# 05_IO_CONN.net
KiCad netlist of a schematic drawn in Altium Designer
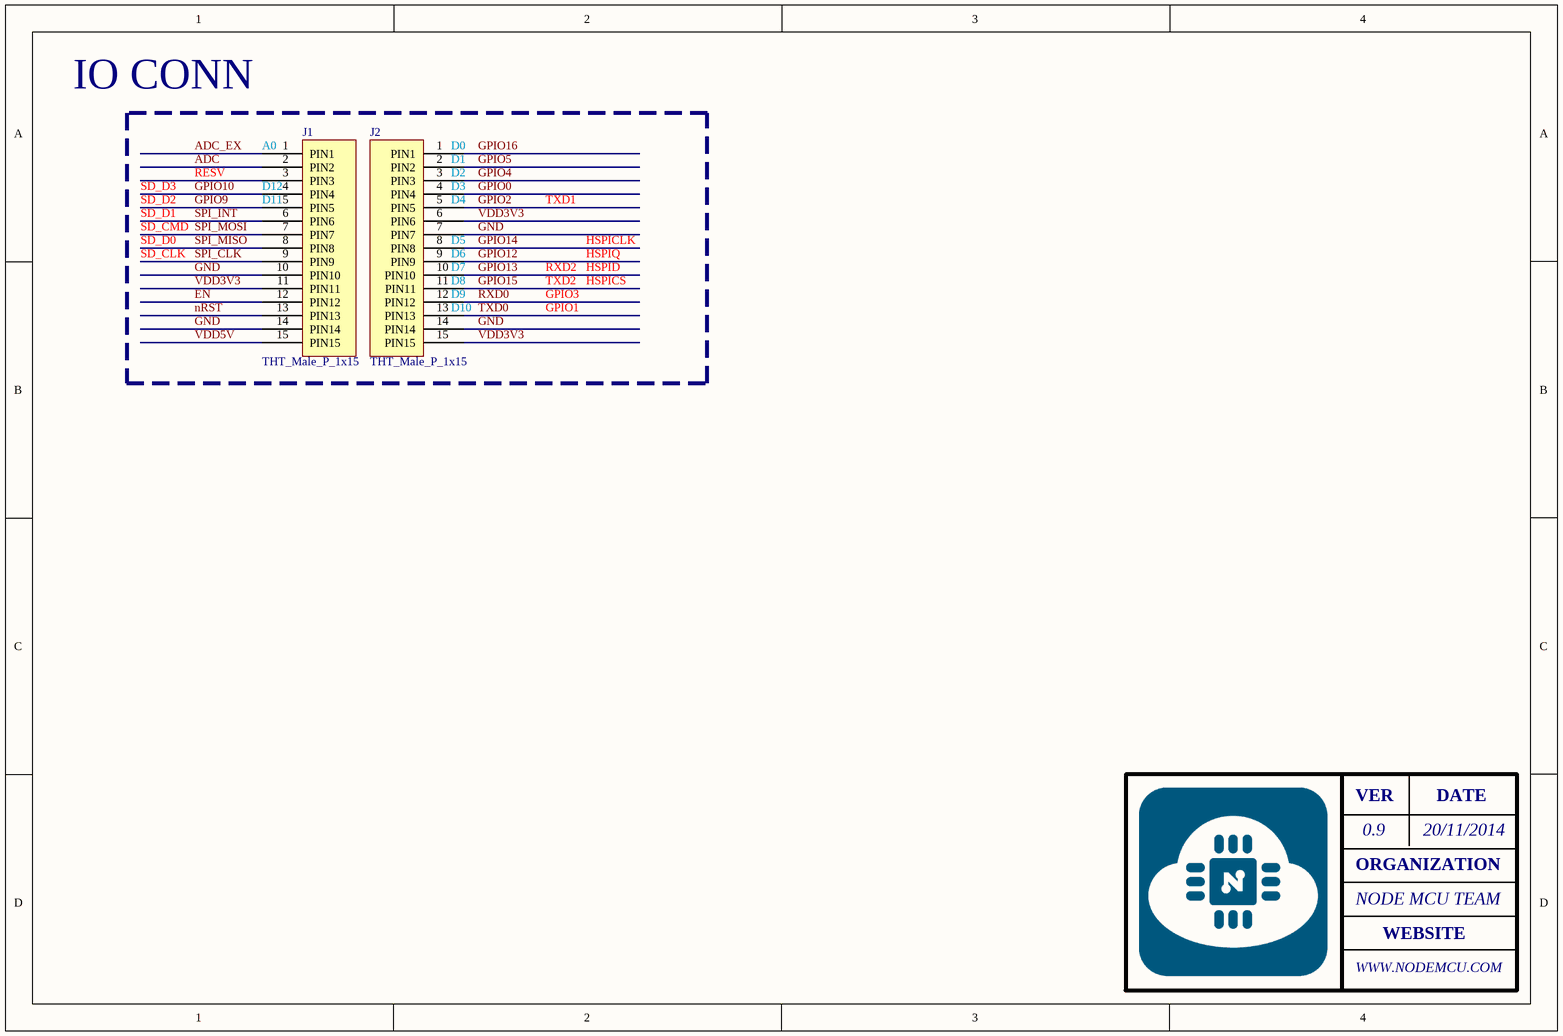
[diagram p0: 05_IO_CONN.SchDoc]

(export (version "E")
  (design (tool "Eeschema 10.0.6"))
  (components
    (comp (ref "J1")
      (value "THT_Male_P_1x15")
      (footprint "THT_Male_P_1x15-2.54mm")
      (description "THT Male pin header strip 1x15")
      (libsource (lib "") (part "THT_Male_P_1x15_1"))
    )
    (comp (ref "J2")
      (value "THT_Male_P_1x15")
      (footprint "THT_Male_P_1x15-2.54mm")
      (description "THT Male pin header strip 1x15")
      (libsource (lib "Vowstar_Connector") (part "THT_Male_P_1x15"))
    )
  )
  (nets
    (net (code "1") (name "/ADC") (class "Default")
      (node (ref "J1") (pin "2") (pinfunction "PIN2_2") (pintype "passive"))
    )
    (net (code "2") (name "/ADC_EX") (class "Default")
      (node (ref "J1") (pin "1") (pinfunction "PIN1_1") (pintype "passive"))
    )
    (net (code "3") (name "/EN") (class "Default")
      (node (ref "J1") (pin "12") (pinfunction "PIN12_12") (pintype "passive"))
    )
    (net (code "4") (name "/GND") (class "Default")
      (node (ref "J1") (pin "10") (pinfunction "PIN10_10") (pintype "passive"))
      (node (ref "J1") (pin "14") (pinfunction "PIN14_14") (pintype "passive"))
      (node (ref "J2") (pin "14") (pinfunction "PIN14_14") (pintype "passive"))
      (node (ref "J2") (pin "7") (pinfunction "PIN7_7") (pintype "passive"))
    )
    (net (code "5") (name "/GPIO0") (class "Default")
      (node (ref "J2") (pin "4") (pinfunction "PIN4_4") (pintype "passive"))
    )
    (net (code "6") (name "/GPIO2") (class "Default")
      (node (ref "J2") (pin "5") (pinfunction "PIN5_5") (pintype "passive"))
    )
    (net (code "7") (name "/GPIO4") (class "Default")
      (node (ref "J2") (pin "3") (pinfunction "PIN3_3") (pintype "passive"))
    )
    (net (code "8") (name "/GPIO5") (class "Default")
      (node (ref "J2") (pin "2") (pinfunction "PIN2_2") (pintype "passive"))
    )
    (net (code "9") (name "/GPIO9") (class "Default")
      (node (ref "J1") (pin "5") (pinfunction "PIN5_5") (pintype "passive"))
    )
    (net (code "10") (name "/GPIO10") (class "Default")
      (node (ref "J1") (pin "4") (pinfunction "PIN4_4") (pintype "passive"))
    )
    (net (code "11") (name "/GPIO12") (class "Default")
      (node (ref "J2") (pin "9") (pinfunction "PIN9_9") (pintype "passive"))
    )
    (net (code "12") (name "/GPIO13") (class "Default")
      (node (ref "J2") (pin "10") (pinfunction "PIN10_10") (pintype "passive"))
    )
    (net (code "13") (name "/GPIO14") (class "Default")
      (node (ref "J2") (pin "8") (pinfunction "PIN8_8") (pintype "passive"))
    )
    (net (code "14") (name "/GPIO15") (class "Default")
      (node (ref "J2") (pin "11") (pinfunction "PIN11_11") (pintype "passive"))
    )
    (net (code "15") (name "/GPIO16") (class "Default")
      (node (ref "J2") (pin "1") (pinfunction "PIN1_1") (pintype "passive"))
    )
    (net (code "16") (name "/RXD0") (class "Default")
      (node (ref "J2") (pin "12") (pinfunction "PIN12_12") (pintype "passive"))
    )
    (net (code "17") (name "/SPI_CLK") (class "Default")
      (node (ref "J1") (pin "9") (pinfunction "PIN9_9") (pintype "passive"))
    )
    (net (code "18") (name "/SPI_INT") (class "Default")
      (node (ref "J1") (pin "6") (pinfunction "PIN6_6") (pintype "passive"))
    )
    (net (code "19") (name "/SPI_MISO") (class "Default")
      (node (ref "J1") (pin "8") (pinfunction "PIN8_8") (pintype "passive"))
    )
    (net (code "20") (name "/SPI_MOSI") (class "Default")
      (node (ref "J1") (pin "7") (pinfunction "PIN7_7") (pintype "passive"))
    )
    (net (code "21") (name "/TXD0") (class "Default")
      (node (ref "J2") (pin "13") (pinfunction "PIN13_13") (pintype "passive"))
    )
    (net (code "22") (name "/VDD3V3") (class "Default")
      (node (ref "J1") (pin "11") (pinfunction "PIN11_11") (pintype "passive"))
      (node (ref "J2") (pin "15") (pinfunction "PIN15_15") (pintype "passive"))
      (node (ref "J2") (pin "6") (pinfunction "PIN6_6") (pintype "passive"))
    )
    (net (code "23") (name "/VDD5V") (class "Default")
      (node (ref "J1") (pin "15") (pinfunction "PIN15_15") (pintype "passive"))
    )
    (net (code "24") (name "/nRST") (class "Default")
      (node (ref "J1") (pin "13") (pinfunction "PIN13_13") (pintype "passive"))
    )
    (net (code "25") (name "unconnected-(J1-PIN3-Pad3)") (class "Default")
      (node (ref "J1") (pin "3") (pinfunction "PIN3_3") (pintype "passive"))
    )
  )
)
